# HV_DAC_8ch_FPGA_LVDS.net
KiCad netlist of a schematic drawn in Altium Designer
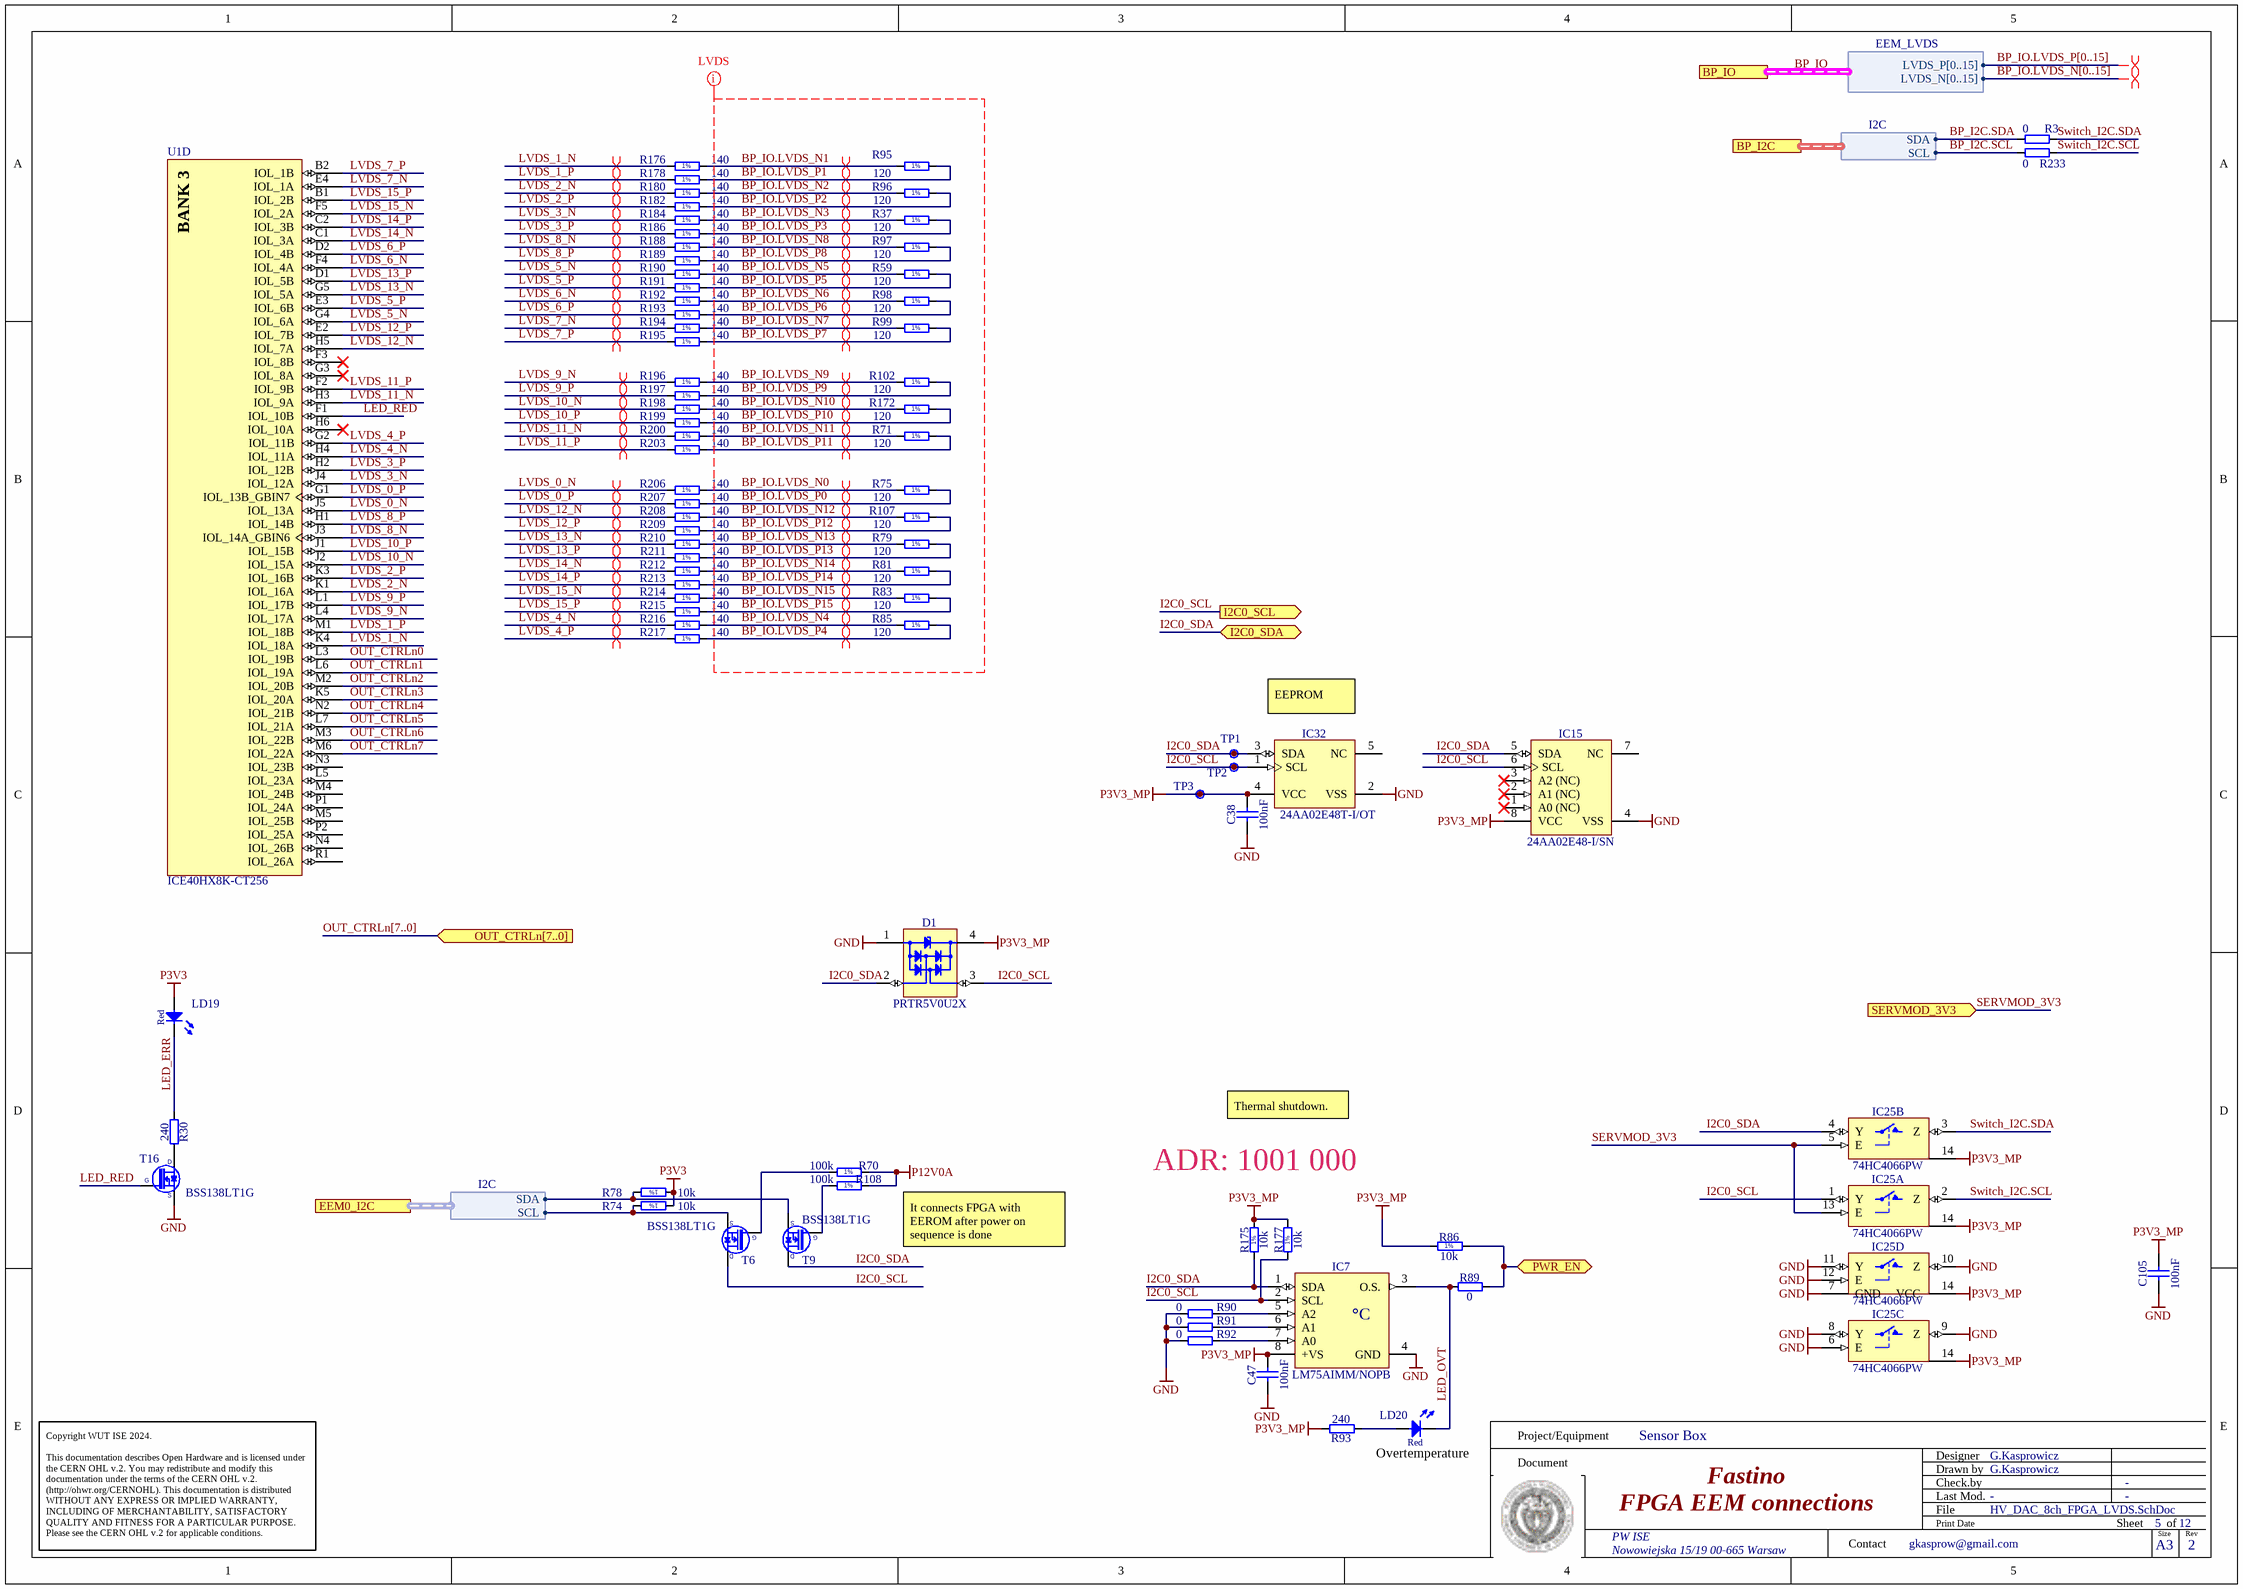
[diagram p0: HV_DAC_8ch_FPGA_LVDS.SchDoc]

(export (version "E")
  (design (tool "Eeschema 10.0.6"))
  (components
    (comp (ref "C38")
      (value "100nF")
      (footprint "CAPC1005X55N")
      (description "Non-polarised capacitor")
      (fields
        (field (name "PART NUMBER") "CC0402_100NF_16V_10%_X5R")
        (field (name "VOLTAGE") "16V")
        (field (name "AUTHOR") "CERN DEM JLC")
      )
      (libsource (lib "Capacitors") (part "Capacitor - non polarized"))
    )
    (comp (ref "C47")
      (value "100nF")
      (footprint "CAPC1005X55N")
      (description "Non-polarised capacitor")
      (fields
        (field (name "PART NUMBER") "CC0402_100NF_16V_10%_X5R")
        (field (name "VOLTAGE") "16V")
        (field (name "AUTHOR") "CERN DEM JLC")
      )
      (libsource (lib "Capacitors") (part "Capacitor - non polarized"))
    )
    (comp (ref "C105")
      (value "100nF")
      (footprint "CAPC1005X55N")
      (description "Non-polarised capacitor")
      (fields
        (field (name "PART NUMBER") "CC0402_100NF_16V_10%_X5R")
        (field (name "VOLTAGE") "16V")
        (field (name "AUTHOR") "CERN DEM JLC")
      )
      (libsource (lib "Capacitors") (part "Capacitor - non polarized"))
    )
    (comp (ref "D1")
      (value "PRTR5V0U2X")
      (footprint "SOT190P230X110-4N")
      (description "Ultra Low Capacitance Double Rail-to-Rail ESD Protection Diode")
      (fields
        (field (name "VOLTAGE") "5.5V")
        (field (name "MANUFACTURER") "NXP SEMICONDUCTORS")
        (field (name "AUTHOR") "CERN DEM JLC")
      )
      (libsource (lib "ICs And Semiconductors") (part "PRTR5V0U2X"))
    )
    (comp (ref "IC7")
      (value "LM75AIMM/NOPB")
      (footprint "SOP65P490X109-8N")
      (description "Digital Temperature Sensor and Thermal Watchdog with Two-Wire Interface")
      (fields (field (name "MANUFACTURER") "TEXAS INSTRUMENTS") (field (name "AUTHOR") "CERN DEM JLC"))
      (libsource (lib "ICs And Semiconductors") (part "LM75"))
    )
    (comp (ref "IC15")
      (value "24AA02E48-I/SN")
      (footprint "SOIC127P600X175-8N")
      (description "1.7V-5.5V, 2K I2C™ Serial EEPROMs with EUI-48™ Node Identity")
      (fields (field (name "MANUFACTURER") "MICROCHIP TECHNOLOGY") (field (name "AUTHOR") "CERN DEM MR"))
      (libsource (lib "ICS-logic") (part "MEM_24AA02E48-I/SN"))
    )
    (comp (ref "IC25")
      (value "74HC4066PW")
      (footprint "SOP65P640X110-14N")
      (fields (field (name "MANUFACTURER") "NXP SEMICONDUCTORS") (field (name "AUTHOR") "CERN DEM JLC"))
      (libsource (lib "ICs And Semiconductors") (part "4066"))
    )
    (comp (ref "IC32")
      (value "24AA02E48T-I/OT")
      (footprint "SOT95P280X145-5N")
      (description "1.7V-5.5V, 2K I2C Serial EEPROM With EUI-48 Node Identity")
      (fields (field (name "MANUFACTURER") "MICROCHIP TECHNOLOGY") (field (name "AUTHOR") "CERN DEM MR"))
      (libsource (lib "ICs And Semiconductors") (part "24AA02E48T-I/OT"))
    )
    (comp (ref "LD19")
      (value "Red")
      (footprint "LED_AVAGO_HSMC-C120")
      (description "LED Red 1C 2A")
      (fields
        (field (name "PART NUMBER") "LED_AVAGO_HSMC-C120")
        (field (name "MANUFACTURER") "AVAGO TECHNOLOGIES")
        (field (name "AUTHOR") "CERN DEM JMW")
      )
      (libsource (lib "ICs And Semiconductors") (part "LED Red 1C 2A"))
    )
    (comp (ref "LD20")
      (value "Red")
      (footprint "LED_AVAGO_HSMC-C120")
      (description "LED Red 1C 2A")
      (fields
        (field (name "PART NUMBER") "LED_AVAGO_HSMC-C120")
        (field (name "MANUFACTURER") "AVAGO TECHNOLOGIES")
        (field (name "AUTHOR") "CERN DEM JMW")
      )
      (libsource (lib "ICs And Semiconductors") (part "LED Red 1C 2A"))
    )
    (comp (ref "R3")
      (value "0")
      (footprint "RESC1005X40N")
      (description "Resistor")
      (fields
        (field (name "PART NUMBER") "R0402_0R_JUMPER")
        (field (name "MANUFACTURER") "GENERIC")
        (field (name "AUTHOR") "CERN DEM JLC")
      )
      (libsource (lib "Resistors") (part "Resistor"))
    )
    (comp (ref "R30")
      (value "240")
      (footprint "RESC1005X40N")
      (description "Resistor - 1%")
      (fields
        (field (name "PART NUMBER") "R0402_240R_1%_0.0625W_100PPM")
        (field (name "POWER") "0.0625W")
        (field (name "AUTHOR") "CERN DEM JLC")
      )
      (libsource (lib "Resistors") (part "Resistor - 1%"))
    )
    (comp (ref "R37")
      (value "120")
      (footprint "RESC1005X40N")
      (description "Resistor - 1%")
      (fields
        (field (name "PART NUMBER") "R0402_120R_1%_0.0625W_100PPM")
        (field (name "POWER") "0.0625W")
        (field (name "AUTHOR") "CERN DEM JLC")
      )
      (libsource (lib "Resistors") (part "Resistor - 1%"))
    )
    (comp (ref "R59")
      (value "120")
      (footprint "RESC1005X40N")
      (description "Resistor - 1%")
      (fields
        (field (name "PART NUMBER") "R0402_120R_1%_0.0625W_100PPM")
        (field (name "POWER") "0.0625W")
        (field (name "AUTHOR") "CERN DEM JLC")
      )
      (libsource (lib "Resistors") (part "Resistor - 1%"))
    )
    (comp (ref "R70")
      (value "100k")
      (footprint "RESC1005X40N")
      (description "Resistor - 1%")
      (fields
        (field (name "PART NUMBER") "R0402_100K_1%_0.0625W_100PPM")
        (field (name "POWER") "0.0625W")
        (field (name "AUTHOR") "CERN DEM JLC")
      )
      (libsource (lib "Resistors") (part "Resistor - 1%"))
    )
    (comp (ref "R71")
      (value "120")
      (footprint "RESC1005X40N")
      (description "Resistor - 1%")
      (fields
        (field (name "PART NUMBER") "R0402_120R_1%_0.0625W_100PPM")
        (field (name "POWER") "0.0625W")
        (field (name "AUTHOR") "CERN DEM JLC")
      )
      (libsource (lib "Resistors") (part "Resistor - 1%"))
    )
    (comp (ref "R74")
      (value "10k")
      (footprint "RESC1005X40N")
      (description "Resistor - 1%")
      (fields
        (field (name "PART NUMBER") "R0402_10K_1%_0.0625W_100PPM")
        (field (name "POWER") "0.0625W")
        (field (name "AUTHOR") "CERN DEM JLC")
      )
      (libsource (lib "Resistors") (part "Resistor - 1%"))
    )
    (comp (ref "R75")
      (value "120")
      (footprint "RESC1005X40N")
      (description "Resistor - 1%")
      (fields
        (field (name "PART NUMBER") "R0402_120R_1%_0.0625W_100PPM")
        (field (name "POWER") "0.0625W")
        (field (name "AUTHOR") "CERN DEM JLC")
      )
      (libsource (lib "Resistors") (part "Resistor - 1%"))
    )
    (comp (ref "R78")
      (value "10k")
      (footprint "RESC1005X40N")
      (description "Resistor - 1%")
      (fields
        (field (name "PART NUMBER") "R0402_10K_1%_0.0625W_100PPM")
        (field (name "POWER") "0.0625W")
        (field (name "AUTHOR") "CERN DEM JLC")
      )
      (libsource (lib "Resistors") (part "Resistor - 1%"))
    )
    (comp (ref "R79")
      (value "120")
      (footprint "RESC1005X40N")
      (description "Resistor - 1%")
      (fields
        (field (name "PART NUMBER") "R0402_120R_1%_0.0625W_100PPM")
        (field (name "POWER") "0.0625W")
        (field (name "AUTHOR") "CERN DEM JLC")
      )
      (libsource (lib "Resistors") (part "Resistor - 1%"))
    )
    (comp (ref "R81")
      (value "120")
      (footprint "RESC1005X40N")
      (description "Resistor - 1%")
      (fields
        (field (name "PART NUMBER") "R0402_120R_1%_0.0625W_100PPM")
        (field (name "POWER") "0.0625W")
        (field (name "AUTHOR") "CERN DEM JLC")
      )
      (libsource (lib "Resistors") (part "Resistor - 1%"))
    )
    (comp (ref "R83")
      (value "120")
      (footprint "RESC1005X40N")
      (description "Resistor - 1%")
      (fields
        (field (name "PART NUMBER") "R0402_120R_1%_0.0625W_100PPM")
        (field (name "POWER") "0.0625W")
        (field (name "AUTHOR") "CERN DEM JLC")
      )
      (libsource (lib "Resistors") (part "Resistor - 1%"))
    )
    (comp (ref "R85")
      (value "120")
      (footprint "RESC1005X40N")
      (description "Resistor - 1%")
      (fields
        (field (name "PART NUMBER") "R0402_120R_1%_0.0625W_100PPM")
        (field (name "POWER") "0.0625W")
        (field (name "AUTHOR") "CERN DEM JLC")
      )
      (libsource (lib "Resistors") (part "Resistor - 1%"))
    )
    (comp (ref "R86")
      (value "10k")
      (footprint "RESC1005X40N")
      (description "Resistor - 1%")
      (fields
        (field (name "PART NUMBER") "R0402_10K_1%_0.0625W_100PPM")
        (field (name "POWER") "0.0625W")
        (field (name "AUTHOR") "CERN DEM JLC")
      )
      (libsource (lib "Resistors") (part "Resistor - 1%"))
    )
    (comp (ref "R89")
      (value "0")
      (footprint "RESC1005X40N")
      (description "Resistor")
      (fields
        (field (name "PART NUMBER") "R0402_0R_JUMPER")
        (field (name "MANUFACTURER") "GENERIC")
        (field (name "AUTHOR") "CERN DEM JLC")
      )
      (libsource (lib "Resistors") (part "Resistor"))
    )
    (comp (ref "R90")
      (value "0")
      (footprint "RESC1005X40N")
      (description "Resistor")
      (fields
        (field (name "PART NUMBER") "R0402_0R_JUMPER")
        (field (name "MANUFACTURER") "GENERIC")
        (field (name "AUTHOR") "CERN DEM JLC")
      )
      (libsource (lib "Resistors") (part "Resistor"))
    )
    (comp (ref "R91")
      (value "0")
      (footprint "RESC1005X40N")
      (description "Resistor")
      (fields
        (field (name "PART NUMBER") "R0402_0R_JUMPER")
        (field (name "MANUFACTURER") "GENERIC")
        (field (name "AUTHOR") "CERN DEM JLC")
      )
      (libsource (lib "Resistors") (part "Resistor"))
    )
    (comp (ref "R92")
      (value "0")
      (footprint "RESC1005X40N")
      (description "Resistor")
      (fields
        (field (name "PART NUMBER") "R0402_0R_JUMPER")
        (field (name "MANUFACTURER") "GENERIC")
        (field (name "AUTHOR") "CERN DEM JLC")
      )
      (libsource (lib "Resistors") (part "Resistor"))
    )
    (comp (ref "R93")
      (value "240")
      (footprint "RESC1005X40N")
      (description "Resistor - 1%")
      (fields
        (field (name "PART NUMBER") "R0402_240R_1%_0.0625W_100PPM")
        (field (name "POWER") "0.0625W")
        (field (name "AUTHOR") "CERN DEM JLC")
      )
      (libsource (lib "Resistors") (part "Resistor - 1%"))
    )
    (comp (ref "R95")
      (value "120")
      (footprint "RESC1005X40N")
      (description "Resistor - 1%")
      (fields
        (field (name "PART NUMBER") "R0402_120R_1%_0.0625W_100PPM")
        (field (name "POWER") "0.0625W")
        (field (name "AUTHOR") "CERN DEM JLC")
      )
      (libsource (lib "Resistors") (part "Resistor - 1%"))
    )
    (comp (ref "R96")
      (value "120")
      (footprint "RESC1005X40N")
      (description "Resistor - 1%")
      (fields
        (field (name "PART NUMBER") "R0402_120R_1%_0.0625W_100PPM")
        (field (name "POWER") "0.0625W")
        (field (name "AUTHOR") "CERN DEM JLC")
      )
      (libsource (lib "Resistors") (part "Resistor - 1%"))
    )
    (comp (ref "R97")
      (value "120")
      (footprint "RESC1005X40N")
      (description "Resistor - 1%")
      (fields
        (field (name "PART NUMBER") "R0402_120R_1%_0.0625W_100PPM")
        (field (name "POWER") "0.0625W")
        (field (name "AUTHOR") "CERN DEM JLC")
      )
      (libsource (lib "Resistors") (part "Resistor - 1%"))
    )
    (comp (ref "R98")
      (value "120")
      (footprint "RESC1005X40N")
      (description "Resistor - 1%")
      (fields
        (field (name "PART NUMBER") "R0402_120R_1%_0.0625W_100PPM")
        (field (name "POWER") "0.0625W")
        (field (name "AUTHOR") "CERN DEM JLC")
      )
      (libsource (lib "Resistors") (part "Resistor - 1%"))
    )
    (comp (ref "R99")
      (value "120")
      (footprint "RESC1005X40N")
      (description "Resistor - 1%")
      (fields
        (field (name "PART NUMBER") "R0402_120R_1%_0.0625W_100PPM")
        (field (name "POWER") "0.0625W")
        (field (name "AUTHOR") "CERN DEM JLC")
      )
      (libsource (lib "Resistors") (part "Resistor - 1%"))
    )
    (comp (ref "R102")
      (value "120")
      (footprint "RESC1005X40N")
      (description "Resistor - 1%")
      (fields
        (field (name "PART NUMBER") "R0402_120R_1%_0.0625W_100PPM")
        (field (name "POWER") "0.0625W")
        (field (name "AUTHOR") "CERN DEM JLC")
      )
      (libsource (lib "Resistors") (part "Resistor - 1%"))
    )
    (comp (ref "R107")
      (value "120")
      (footprint "RESC1005X40N")
      (description "Resistor - 1%")
      (fields
        (field (name "PART NUMBER") "R0402_120R_1%_0.0625W_100PPM")
        (field (name "POWER") "0.0625W")
        (field (name "AUTHOR") "CERN DEM JLC")
      )
      (libsource (lib "Resistors") (part "Resistor - 1%"))
    )
    (comp (ref "R108")
      (value "100k")
      (footprint "RESC1005X40N")
      (description "Resistor - 1%")
      (fields
        (field (name "PART NUMBER") "R0402_100K_1%_0.0625W_100PPM")
        (field (name "POWER") "0.0625W")
        (field (name "AUTHOR") "CERN DEM JLC")
      )
      (libsource (lib "Resistors") (part "Resistor - 1%"))
    )
    (comp (ref "R172")
      (value "120")
      (footprint "RESC1005X40N")
      (description "Resistor - 1%")
      (fields
        (field (name "PART NUMBER") "R0402_120R_1%_0.0625W_100PPM")
        (field (name "POWER") "0.0625W")
        (field (name "AUTHOR") "CERN DEM JLC")
      )
      (libsource (lib "Resistors") (part "Resistor - 1%"))
    )
    (comp (ref "R175")
      (value "10k")
      (footprint "RESC1005X40N")
      (description "Resistor - 1%")
      (fields
        (field (name "PART NUMBER") "R0402_10K_1%_0.0625W_100PPM")
        (field (name "POWER") "0.0625W")
        (field (name "AUTHOR") "CERN DEM JLC")
      )
      (libsource (lib "Resistors") (part "Resistor - 1%"))
    )
    (comp (ref "R176")
      (value "140")
      (footprint "RESC0603X28N")
      (description "Resistor - 1%")
      (fields
        (field (name "PART NUMBER") "R0201_140R_1%_0.05W_200PPM")
        (field (name "POWER") "0.05W")
        (field (name "AUTHOR") "CERN DEM MR")
      )
      (libsource (lib "Resistors") (part "Resistor - 1%"))
    )
    (comp (ref "R177")
      (value "10k")
      (footprint "RESC1005X40N")
      (description "Resistor - 1%")
      (fields
        (field (name "PART NUMBER") "R0402_10K_1%_0.0625W_100PPM")
        (field (name "POWER") "0.0625W")
        (field (name "AUTHOR") "CERN DEM JLC")
      )
      (libsource (lib "Resistors") (part "Resistor - 1%"))
    )
    (comp (ref "R178")
      (value "140")
      (footprint "RESC0603X28N")
      (description "Resistor - 1%")
      (fields
        (field (name "PART NUMBER") "R0201_140R_1%_0.05W_200PPM")
        (field (name "POWER") "0.05W")
        (field (name "AUTHOR") "CERN DEM MR")
      )
      (libsource (lib "Resistors") (part "Resistor - 1%"))
    )
    (comp (ref "R180")
      (value "140")
      (footprint "RESC0603X28N")
      (description "Resistor - 1%")
      (fields
        (field (name "PART NUMBER") "R0201_140R_1%_0.05W_200PPM")
        (field (name "POWER") "0.05W")
        (field (name "AUTHOR") "CERN DEM MR")
      )
      (libsource (lib "Resistors") (part "Resistor - 1%"))
    )
    (comp (ref "R182")
      (value "140")
      (footprint "RESC0603X28N")
      (description "Resistor - 1%")
      (fields
        (field (name "PART NUMBER") "R0201_140R_1%_0.05W_200PPM")
        (field (name "POWER") "0.05W")
        (field (name "AUTHOR") "CERN DEM MR")
      )
      (libsource (lib "Resistors") (part "Resistor - 1%"))
    )
    (comp (ref "R184")
      (value "140")
      (footprint "RESC0603X28N")
      (description "Resistor - 1%")
      (fields
        (field (name "PART NUMBER") "R0201_140R_1%_0.05W_200PPM")
        (field (name "POWER") "0.05W")
        (field (name "AUTHOR") "CERN DEM MR")
      )
      (libsource (lib "Resistors") (part "Resistor - 1%"))
    )
    (comp (ref "R186")
      (value "140")
      (footprint "RESC0603X28N")
      (description "Resistor - 1%")
      (fields
        (field (name "PART NUMBER") "R0201_140R_1%_0.05W_200PPM")
        (field (name "POWER") "0.05W")
        (field (name "AUTHOR") "CERN DEM MR")
      )
      (libsource (lib "Resistors") (part "Resistor - 1%"))
    )
    (comp (ref "R188")
      (value "140")
      (footprint "RESC0603X28N")
      (description "Resistor - 1%")
      (fields
        (field (name "PART NUMBER") "R0201_140R_1%_0.05W_200PPM")
        (field (name "POWER") "0.05W")
        (field (name "AUTHOR") "CERN DEM MR")
      )
      (libsource (lib "Resistors") (part "Resistor - 1%"))
    )
    (comp (ref "R189")
      (value "140")
      (footprint "RESC0603X28N")
      (description "Resistor - 1%")
      (fields
        (field (name "PART NUMBER") "R0201_140R_1%_0.05W_200PPM")
        (field (name "POWER") "0.05W")
        (field (name "AUTHOR") "CERN DEM MR")
      )
      (libsource (lib "Resistors") (part "Resistor - 1%"))
    )
    (comp (ref "R190")
      (value "140")
      (footprint "RESC0603X28N")
      (description "Resistor - 1%")
      (fields
        (field (name "PART NUMBER") "R0201_140R_1%_0.05W_200PPM")
        (field (name "POWER") "0.05W")
        (field (name "AUTHOR") "CERN DEM MR")
      )
      (libsource (lib "Resistors") (part "Resistor - 1%"))
    )
    (comp (ref "R191")
      (value "140")
      (footprint "RESC0603X28N")
      (description "Resistor - 1%")
      (fields
        (field (name "PART NUMBER") "R0201_140R_1%_0.05W_200PPM")
        (field (name "POWER") "0.05W")
        (field (name "AUTHOR") "CERN DEM MR")
      )
      (libsource (lib "Resistors") (part "Resistor - 1%"))
    )
    (comp (ref "R192")
      (value "140")
      (footprint "RESC0603X28N")
      (description "Resistor - 1%")
      (fields
        (field (name "PART NUMBER") "R0201_140R_1%_0.05W_200PPM")
        (field (name "POWER") "0.05W")
        (field (name "AUTHOR") "CERN DEM MR")
      )
      (libsource (lib "Resistors") (part "Resistor - 1%"))
    )
    (comp (ref "R193")
      (value "140")
      (footprint "RESC0603X28N")
      (description "Resistor - 1%")
      (fields
        (field (name "PART NUMBER") "R0201_140R_1%_0.05W_200PPM")
        (field (name "POWER") "0.05W")
        (field (name "AUTHOR") "CERN DEM MR")
      )
      (libsource (lib "Resistors") (part "Resistor - 1%"))
    )
    (comp (ref "R194")
      (value "140")
      (footprint "RESC0603X28N")
      (description "Resistor - 1%")
      (fields
        (field (name "PART NUMBER") "R0201_140R_1%_0.05W_200PPM")
        (field (name "POWER") "0.05W")
        (field (name "AUTHOR") "CERN DEM MR")
      )
      (libsource (lib "Resistors") (part "Resistor - 1%"))
    )
    (comp (ref "R195")
      (value "140")
      (footprint "RESC0603X28N")
      (description "Resistor - 1%")
      (fields
        (field (name "PART NUMBER") "R0201_140R_1%_0.05W_200PPM")
        (field (name "POWER") "0.05W")
        (field (name "AUTHOR") "CERN DEM MR")
      )
      (libsource (lib "Resistors") (part "Resistor - 1%"))
    )
    (comp (ref "R196")
      (value "140")
      (footprint "RESC0603X28N")
      (description "Resistor - 1%")
      (fields
        (field (name "PART NUMBER") "R0201_140R_1%_0.05W_200PPM")
        (field (name "POWER") "0.05W")
        (field (name "AUTHOR") "CERN DEM MR")
      )
      (libsource (lib "Resistors") (part "Resistor - 1%"))
    )
    (comp (ref "R197")
      (value "140")
      (footprint "RESC0603X28N")
      (description "Resistor - 1%")
      (fields
        (field (name "PART NUMBER") "R0201_140R_1%_0.05W_200PPM")
        (field (name "POWER") "0.05W")
        (field (name "AUTHOR") "CERN DEM MR")
      )
      (libsource (lib "Resistors") (part "Resistor - 1%"))
    )
    (comp (ref "R198")
      (value "140")
      (footprint "RESC0603X28N")
      (description "Resistor - 1%")
      (fields
        (field (name "PART NUMBER") "R0201_140R_1%_0.05W_200PPM")
        (field (name "POWER") "0.05W")
        (field (name "AUTHOR") "CERN DEM MR")
      )
      (libsource (lib "Resistors") (part "Resistor - 1%"))
    )
    (comp (ref "R199")
      (value "140")
      (footprint "RESC0603X28N")
      (description "Resistor - 1%")
      (fields
        (field (name "PART NUMBER") "R0201_140R_1%_0.05W_200PPM")
        (field (name "POWER") "0.05W")
        (field (name "AUTHOR") "CERN DEM MR")
      )
      (libsource (lib "Resistors") (part "Resistor - 1%"))
    )
    (comp (ref "R200")
      (value "140")
      (footprint "RESC0603X28N")
      (description "Resistor - 1%")
      (fields
        (field (name "PART NUMBER") "R0201_140R_1%_0.05W_200PPM")
        (field (name "POWER") "0.05W")
        (field (name "AUTHOR") "CERN DEM MR")
      )
      (libsource (lib "Resistors") (part "Resistor - 1%"))
    )
    (comp (ref "R203")
      (value "140")
      (footprint "RESC0603X28N")
      (description "Resistor - 1%")
      (fields
        (field (name "PART NUMBER") "R0201_140R_1%_0.05W_200PPM")
        (field (name "POWER") "0.05W")
        (field (name "AUTHOR") "CERN DEM MR")
      )
      (libsource (lib "Resistors") (part "Resistor - 1%"))
    )
    (comp (ref "R206")
      (value "140")
      (footprint "RESC0603X28N")
      (description "Resistor - 1%")
      (fields
        (field (name "PART NUMBER") "R0201_140R_1%_0.05W_200PPM")
        (field (name "POWER") "0.05W")
        (field (name "AUTHOR") "CERN DEM MR")
      )
      (libsource (lib "Resistors") (part "Resistor - 1%"))
    )
    (comp (ref "R207")
      (value "140")
      (footprint "RESC0603X28N")
      (description "Resistor - 1%")
      (fields
        (field (name "PART NUMBER") "R0201_140R_1%_0.05W_200PPM")
        (field (name "POWER") "0.05W")
        (field (name "AUTHOR") "CERN DEM MR")
      )
      (libsource (lib "Resistors") (part "Resistor - 1%"))
    )
    (comp (ref "R208")
      (value "140")
      (footprint "RESC0603X28N")
      (description "Resistor - 1%")
      (fields
        (field (name "PART NUMBER") "R0201_140R_1%_0.05W_200PPM")
        (field (name "POWER") "0.05W")
        (field (name "AUTHOR") "CERN DEM MR")
      )
      (libsource (lib "Resistors") (part "Resistor - 1%"))
    )
    (comp (ref "R209")
      (value "140")
      (footprint "RESC0603X28N")
      (description "Resistor - 1%")
      (fields
        (field (name "PART NUMBER") "R0201_140R_1%_0.05W_200PPM")
        (field (name "POWER") "0.05W")
        (field (name "AUTHOR") "CERN DEM MR")
      )
      (libsource (lib "Resistors") (part "Resistor - 1%"))
    )
    (comp (ref "R210")
      (value "140")
      (footprint "RESC0603X28N")
      (description "Resistor - 1%")
      (fields
        (field (name "PART NUMBER") "R0201_140R_1%_0.05W_200PPM")
        (field (name "POWER") "0.05W")
        (field (name "AUTHOR") "CERN DEM MR")
      )
      (libsource (lib "Resistors") (part "Resistor - 1%"))
    )
    (comp (ref "R211")
      (value "140")
      (footprint "RESC0603X28N")
      (description "Resistor - 1%")
      (fields
        (field (name "PART NUMBER") "R0201_140R_1%_0.05W_200PPM")
        (field (name "POWER") "0.05W")
        (field (name "AUTHOR") "CERN DEM MR")
      )
      (libsource (lib "Resistors") (part "Resistor - 1%"))
    )
    (comp (ref "R212")
      (value "140")
      (footprint "RESC0603X28N")
      (description "Resistor - 1%")
      (fields
        (field (name "PART NUMBER") "R0201_140R_1%_0.05W_200PPM")
        (field (name "POWER") "0.05W")
        (field (name "AUTHOR") "CERN DEM MR")
      )
      (libsource (lib "Resistors") (part "Resistor - 1%"))
    )
    (comp (ref "R213")
      (value "140")
      (footprint "RESC0603X28N")
      (description "Resistor - 1%")
      (fields
        (field (name "PART NUMBER") "R0201_140R_1%_0.05W_200PPM")
        (field (name "POWER") "0.05W")
        (field (name "AUTHOR") "CERN DEM MR")
      )
      (libsource (lib "Resistors") (part "Resistor - 1%"))
    )
    (comp (ref "R214")
      (value "140")
      (footprint "RESC0603X28N")
      (description "Resistor - 1%")
      (fields
        (field (name "PART NUMBER") "R0201_140R_1%_0.05W_200PPM")
        (field (name "POWER") "0.05W")
        (field (name "AUTHOR") "CERN DEM MR")
      )
      (libsource (lib "Resistors") (part "Resistor - 1%"))
    )
    (comp (ref "R215")
      (value "140")
      (footprint "RESC0603X28N")
      (description "Resistor - 1%")
      (fields
        (field (name "PART NUMBER") "R0201_140R_1%_0.05W_200PPM")
        (field (name "POWER") "0.05W")
        (field (name "AUTHOR") "CERN DEM MR")
      )
      (libsource (lib "Resistors") (part "Resistor - 1%"))
    )
    (comp (ref "R216")
      (value "140")
      (footprint "RESC0603X28N")
      (description "Resistor - 1%")
      (fields
        (field (name "PART NUMBER") "R0201_140R_1%_0.05W_200PPM")
        (field (name "POWER") "0.05W")
        (field (name "AUTHOR") "CERN DEM MR")
      )
      (libsource (lib "Resistors") (part "Resistor - 1%"))
    )
    (comp (ref "R217")
      (value "140")
      (footprint "RESC0603X28N")
      (description "Resistor - 1%")
      (fields
        (field (name "PART NUMBER") "R0201_140R_1%_0.05W_200PPM")
        (field (name "POWER") "0.05W")
        (field (name "AUTHOR") "CERN DEM MR")
      )
      (libsource (lib "Resistors") (part "Resistor - 1%"))
    )
    (comp (ref "R233")
      (value "0")
      (footprint "RESC1005X40N")
      (description "Resistor")
      (fields
        (field (name "PART NUMBER") "R0402_0R_JUMPER")
        (field (name "MANUFACTURER") "GENERIC")
        (field (name "AUTHOR") "CERN DEM JLC")
      )
      (libsource (lib "Resistors") (part "Resistor"))
    )
    (comp (ref "T6")
      (value "BSS138LT1G")
      (footprint "SOT95P240X110-3N")
      (description "N-CHANNEL MOSFET WITH DIODE")
      (fields (field (name "MANUFACTURER") "ON SEMICONDUCTOR") (field (name "AUTHOR") "CERN DEM JLC"))
      (libsource (lib "ICs And Semiconductors") (part "N-MOSFET-D 1G 2S 3D"))
    )
    (comp (ref "T9")
      (value "BSS138LT1G")
      (footprint "SOT95P240X110-3N")
      (description "N-CHANNEL MOSFET WITH DIODE")
      (fields (field (name "MANUFACTURER") "ON SEMICONDUCTOR") (field (name "AUTHOR") "CERN DEM JLC"))
      (libsource (lib "ICs And Semiconductors") (part "N-MOSFET-D 1G 2S 3D"))
    )
    (comp (ref "T16")
      (value "BSS138LT1G")
      (footprint "SOT95P240X110-3N")
      (description "N-CHANNEL MOSFET WITH DIODE")
      (fields (field (name "MANUFACTURER") "ON SEMICONDUCTOR") (field (name "AUTHOR") "CERN DEM JLC"))
      (libsource (lib "") (part "N-MOSFET-D 1G 2S 3D_1"))
    )
    (comp (ref "TP1")
      (value "Test Point")
      (footprint "TPS127")
      (fields (field (name "PART NUMBER") "SMD_PAD_1.27X1.27MM") (field (name "AUTHOR") "CERN DEM JLC"))
      (libsource (lib "Eletro-mechanical") (part "Test Point"))
    )
    (comp (ref "TP2")
      (value "Test Point")
      (footprint "TPS127")
      (fields (field (name "PART NUMBER") "SMD_PAD_1.27X1.27MM") (field (name "AUTHOR") "CERN DEM JLC"))
      (libsource (lib "Eletro-mechanical") (part "Test Point"))
    )
    (comp (ref "TP3")
      (value "Test Point")
      (footprint "TPS127")
      (fields (field (name "PART NUMBER") "SMD_PAD_1.27X1.27MM") (field (name "AUTHOR") "CERN DEM JLC"))
      (libsource (lib "Eletro-mechanical") (part "Test Point"))
    )
    (comp (ref "U1")
      (value "ICE40HX8K-CT256")
      (footprint "LATC-caBGA-256")
      (fields (field (name "MANUFACTURER") "Lattice Semiconductor"))
      (libsource (lib "Altium Content Vault") (part "LATC-HX8K-caBGA-256"))
    )
  )
  (nets
    (net (code "3") (name "/BP_I2C.SCL") (class "Default")
      (node (ref "R233") (pin "1") (pinfunction "1_1") (pintype "passive"))
    )
    (net (code "4") (name "/BP_I2C.SDA") (class "Default")
      (node (ref "R3") (pin "1") (pinfunction "1_1") (pintype "passive"))
    )
    (net (code "5") (name "/BP_IO.LVDS_N0") (class "Default")
      (node (ref "R206") (pin "2") (pinfunction "2_2") (pintype "passive"))
      (node (ref "R75") (pin "1") (pinfunction "1_1") (pintype "passive"))
    )
    (net (code "6") (name "/BP_IO.LVDS_N1") (class "Default")
      (node (ref "R176") (pin "2") (pinfunction "2_2") (pintype "passive"))
      (node (ref "R95") (pin "1") (pinfunction "1_1") (pintype "passive"))
    )
    (net (code "7") (name "/BP_IO.LVDS_N2") (class "Default")
      (node (ref "R180") (pin "2") (pinfunction "2_2") (pintype "passive"))
      (node (ref "R96") (pin "1") (pinfunction "1_1") (pintype "passive"))
    )
    (net (code "8") (name "/BP_IO.LVDS_N3") (class "Default")
      (node (ref "R184") (pin "2") (pinfunction "2_2") (pintype "passive"))
      (node (ref "R37") (pin "1") (pinfunction "1_1") (pintype "passive"))
    )
    (net (code "9") (name "/BP_IO.LVDS_N4") (class "Default")
      (node (ref "R216") (pin "2") (pinfunction "2_2") (pintype "passive"))
      (node (ref "R85") (pin "1") (pinfunction "1_1") (pintype "passive"))
    )
    (net (code "10") (name "/BP_IO.LVDS_N5") (class "Default")
      (node (ref "R190") (pin "2") (pinfunction "2_2") (pintype "passive"))
      (node (ref "R59") (pin "1") (pinfunction "1_1") (pintype "passive"))
    )
    (net (code "11") (name "/BP_IO.LVDS_N6") (class "Default")
      (node (ref "R192") (pin "2") (pinfunction "2_2") (pintype "passive"))
      (node (ref "R98") (pin "1") (pinfunction "1_1") (pintype "passive"))
    )
    (net (code "12") (name "/BP_IO.LVDS_N7") (class "Default")
      (node (ref "R194") (pin "2") (pinfunction "2_2") (pintype "passive"))
      (node (ref "R99") (pin "1") (pinfunction "1_1") (pintype "passive"))
    )
    (net (code "13") (name "/BP_IO.LVDS_N8") (class "Default")
      (node (ref "R188") (pin "2") (pinfunction "2_2") (pintype "passive"))
      (node (ref "R97") (pin "1") (pinfunction "1_1") (pintype "passive"))
    )
    (net (code "14") (name "/BP_IO.LVDS_N9") (class "Default")
      (node (ref "R102") (pin "1") (pinfunction "1_1") (pintype "passive"))
      (node (ref "R196") (pin "2") (pinfunction "2_2") (pintype "passive"))
    )
    (net (code "15") (name "/BP_IO.LVDS_N10") (class "Default")
      (node (ref "R172") (pin "1") (pinfunction "1_1") (pintype "passive"))
      (node (ref "R198") (pin "2") (pinfunction "2_2") (pintype "passive"))
    )
    (net (code "16") (name "/BP_IO.LVDS_N11") (class "Default")
      (node (ref "R200") (pin "2") (pinfunction "2_2") (pintype "passive"))
      (node (ref "R71") (pin "1") (pinfunction "1_1") (pintype "passive"))
    )
    (net (code "17") (name "/BP_IO.LVDS_N12") (class "Default")
      (node (ref "R107") (pin "1") (pinfunction "1_1") (pintype "passive"))
      (node (ref "R208") (pin "2") (pinfunction "2_2") (pintype "passive"))
    )
    (net (code "18") (name "/BP_IO.LVDS_N13") (class "Default")
      (node (ref "R210") (pin "2") (pinfunction "2_2") (pintype "passive"))
      (node (ref "R79") (pin "1") (pinfunction "1_1") (pintype "passive"))
    )
    (net (code "19") (name "/BP_IO.LVDS_N14") (class "Default")
      (node (ref "R212") (pin "2") (pinfunction "2_2") (pintype "passive"))
      (node (ref "R81") (pin "1") (pinfunction "1_1") (pintype "passive"))
    )
    (net (code "20") (name "/BP_IO.LVDS_N15") (class "Default")
      (node (ref "R214") (pin "2") (pinfunction "2_2") (pintype "passive"))
      (node (ref "R83") (pin "1") (pinfunction "1_1") (pintype "passive"))
    )
    (net (code "22") (name "/BP_IO.LVDS_P0") (class "Default")
      (node (ref "R207") (pin "2") (pinfunction "2_2") (pintype "passive"))
      (node (ref "R75") (pin "2") (pinfunction "2_2") (pintype "passive"))
    )
    (net (code "23") (name "/BP_IO.LVDS_P1") (class "Default")
      (node (ref "R178") (pin "2") (pinfunction "2_2") (pintype "passive"))
      (node (ref "R95") (pin "2") (pinfunction "2_2") (pintype "passive"))
    )
    (net (code "24") (name "/BP_IO.LVDS_P2") (class "Default")
      (node (ref "R182") (pin "2") (pinfunction "2_2") (pintype "passive"))
      (node (ref "R96") (pin "2") (pinfunction "2_2") (pintype "passive"))
    )
    (net (code "25") (name "/BP_IO.LVDS_P3") (class "Default")
      (node (ref "R186") (pin "2") (pinfunction "2_2") (pintype "passive"))
      (node (ref "R37") (pin "2") (pinfunction "2_2") (pintype "passive"))
    )
    (net (code "26") (name "/BP_IO.LVDS_P4") (class "Default")
      (node (ref "R217") (pin "2") (pinfunction "2_2") (pintype "passive"))
      (node (ref "R85") (pin "2") (pinfunction "2_2") (pintype "passive"))
    )
    (net (code "27") (name "/BP_IO.LVDS_P5") (class "Default")
      (node (ref "R191") (pin "2") (pinfunction "2_2") (pintype "passive"))
      (node (ref "R59") (pin "2") (pinfunction "2_2") (pintype "passive"))
    )
    (net (code "28") (name "/BP_IO.LVDS_P6") (class "Default")
      (node (ref "R193") (pin "2") (pinfunction "2_2") (pintype "passive"))
      (node (ref "R98") (pin "2") (pinfunction "2_2") (pintype "passive"))
    )
    (net (code "29") (name "/BP_IO.LVDS_P7") (class "Default")
      (node (ref "R195") (pin "2") (pinfunction "2_2") (pintype "passive"))
      (node (ref "R99") (pin "2") (pinfunction "2_2") (pintype "passive"))
    )
    (net (code "30") (name "/BP_IO.LVDS_P8") (class "Default")
      (node (ref "R189") (pin "2") (pinfunction "2_2") (pintype "passive"))
      (node (ref "R97") (pin "2") (pinfunction "2_2") (pintype "passive"))
    )
    (net (code "31") (name "/BP_IO.LVDS_P9") (class "Default")
      (node (ref "R102") (pin "2") (pinfunction "2_2") (pintype "passive"))
      (node (ref "R197") (pin "2") (pinfunction "2_2") (pintype "passive"))
    )
    (net (code "32") (name "/BP_IO.LVDS_P10") (class "Default")
      (node (ref "R172") (pin "2") (pinfunction "2_2") (pintype "passive"))
      (node (ref "R199") (pin "2") (pinfunction "2_2") (pintype "passive"))
    )
    (net (code "33") (name "/BP_IO.LVDS_P11") (class "Default")
      (node (ref "R203") (pin "2") (pinfunction "2_2") (pintype "passive"))
      (node (ref "R71") (pin "2") (pinfunction "2_2") (pintype "passive"))
    )
    (net (code "34") (name "/BP_IO.LVDS_P12") (class "Default")
      (node (ref "R107") (pin "2") (pinfunction "2_2") (pintype "passive"))
      (node (ref "R209") (pin "2") (pinfunction "2_2") (pintype "passive"))
    )
    (net (code "35") (name "/BP_IO.LVDS_P13") (class "Default")
      (node (ref "R211") (pin "2") (pinfunction "2_2") (pintype "passive"))
      (node (ref "R79") (pin "2") (pinfunction "2_2") (pintype "passive"))
    )
    (net (code "36") (name "/BP_IO.LVDS_P14") (class "Default")
      (node (ref "R213") (pin "2") (pinfunction "2_2") (pintype "passive"))
      (node (ref "R81") (pin "2") (pinfunction "2_2") (pintype "passive"))
    )
    (net (code "37") (name "/BP_IO.LVDS_P15") (class "Default")
      (node (ref "R215") (pin "2") (pinfunction "2_2") (pintype "passive"))
      (node (ref "R83") (pin "2") (pinfunction "2_2") (pintype "passive"))
    )
    (net (code "40") (name "/I2C0_SCL") (class "Default")
      (node (ref "D1") (pin "3") (pinfunction "I/O2_3") (pintype "bidirectional"))
      (node (ref "IC15") (pin "6") (pinfunction "SCL_6") (pintype "input"))
      (node (ref "IC25") (pin "1") (pinfunction "Y_1") (pintype "bidirectional"))
      (node (ref "IC32") (pin "1") (pinfunction "SCL_1") (pintype "input"))
      (node (ref "IC7") (pin "2") (pinfunction "SCL_2") (pintype "input"))
      (node (ref "R177") (pin "1") (pinfunction "1_1") (pintype "passive"))
      (node (ref "T6") (pin "3") (pinfunction "D_3") (pintype "passive"))
      (node (ref "TP2") (pin "1") (pinfunction "1_1") (pintype "bidirectional"))
    )
    (net (code "41") (name "/I2C0_SDA") (class "Default")
      (node (ref "D1") (pin "2") (pinfunction "I/O1_2") (pintype "bidirectional"))
      (node (ref "IC15") (pin "5") (pinfunction "SDA_5") (pintype "bidirectional"))
      (node (ref "IC25") (pin "4") (pinfunction "Y_4") (pintype "bidirectional"))
      (node (ref "IC32") (pin "3") (pinfunction "SDA_3") (pintype "bidirectional"))
      (node (ref "IC7") (pin "1") (pinfunction "SDA_1") (pintype "bidirectional"))
      (node (ref "R175") (pin "1") (pinfunction "1_1") (pintype "passive"))
      (node (ref "T9") (pin "3") (pinfunction "D_3") (pintype "passive"))
      (node (ref "TP1") (pin "1") (pinfunction "1_1") (pintype "bidirectional"))
    )
    (net (code "42") (name "/LED_ERR") (class "Default")
      (node (ref "LD19") (pin "1") (pinfunction "C_1") (pintype "passive"))
      (node (ref "R30") (pin "1") (pinfunction "1_1") (pintype "passive"))
    )
    (net (code "43") (name "/LED_OVT") (class "Default")
      (node (ref "IC7") (pin "3") (pinfunction "O.S._3") (pintype "output"))
      (node (ref "LD20") (pin "1") (pinfunction "C_1") (pintype "passive"))
      (node (ref "R89") (pin "1") (pinfunction "1_1") (pintype "passive"))
    )
    (net (code "44") (name "/LED_RED") (class "Default")
      (node (ref "T16") (pin "1") (pinfunction "G_1") (pintype "passive"))
      (node (ref "U1") (pin "F1") (pinfunction "IOL_10B_F1") (pintype "bidirectional"))
    )
    (net (code "45") (name "/LVDS_0_N") (class "Default")
      (node (ref "R206") (pin "1") (pinfunction "1_1") (pintype "passive"))
      (node (ref "U1") (pin "J5") (pinfunction "IOL_13A_J5") (pintype "bidirectional"))
    )
    (net (code "46") (name "/LVDS_0_P") (class "Default")
      (node (ref "R207") (pin "1") (pinfunction "1_1") (pintype "passive"))
      (node (ref "U1") (pin "G1") (pinfunction "IOL_13B_GBIN7_G1") (pintype "bidirectional"))
    )
    (net (code "47") (name "/LVDS_1_N") (class "Default")
      (node (ref "R176") (pin "1") (pinfunction "1_1") (pintype "passive"))
      (node (ref "U1") (pin "K4") (pinfunction "IOL_18A_K4") (pintype "bidirectional"))
    )
    (net (code "48") (name "/LVDS_1_P") (class "Default")
      (node (ref "R178") (pin "1") (pinfunction "1_1") (pintype "passive"))
      (node (ref "U1") (pin "M1") (pinfunction "IOL_18B_M1") (pintype "bidirectional"))
    )
    (net (code "49") (name "/LVDS_2_N") (class "Default")
      (node (ref "R180") (pin "1") (pinfunction "1_1") (pintype "passive"))
      (node (ref "U1") (pin "K1") (pinfunction "IOL_16A_K1") (pintype "bidirectional"))
    )
    (net (code "50") (name "/LVDS_2_P") (class "Default")
      (node (ref "R182") (pin "1") (pinfunction "1_1") (pintype "passive"))
      (node (ref "U1") (pin "K3") (pinfunction "IOL_16B_K3") (pintype "bidirectional"))
    )
    (net (code "51") (name "/LVDS_3_N") (class "Default")
      (node (ref "R184") (pin "1") (pinfunction "1_1") (pintype "passive"))
      (node (ref "U1") (pin "J4") (pinfunction "IOL_12A_J4") (pintype "bidirectional"))
    )
    (net (code "52") (name "/LVDS_3_P") (class "Default")
      (node (ref "R186") (pin "1") (pinfunction "1_1") (pintype "passive"))
      (node (ref "U1") (pin "H2") (pinfunction "IOL_12B_H2") (pintype "bidirectional"))
    )
    (net (code "53") (name "/LVDS_4_N") (class "Default")
      (node (ref "R216") (pin "1") (pinfunction "1_1") (pintype "passive"))
      (node (ref "U1") (pin "H4") (pinfunction "IOL_11A_H4") (pintype "bidirectional"))
    )
    (net (code "54") (name "/LVDS_4_P") (class "Default")
      (node (ref "R217") (pin "1") (pinfunction "1_1") (pintype "passive"))
      (node (ref "U1") (pin "G2") (pinfunction "IOL_11B_G2") (pintype "bidirectional"))
    )
    (net (code "55") (name "/LVDS_5_N") (class "Default")
      (node (ref "R190") (pin "1") (pinfunction "1_1") (pintype "passive"))
      (node (ref "U1") (pin "G4") (pinfunction "IOL_6A_G4") (pintype "bidirectional"))
    )
    (net (code "56") (name "/LVDS_5_P") (class "Default")
      (node (ref "R191") (pin "1") (pinfunction "1_1") (pintype "passive"))
      (node (ref "U1") (pin "E3") (pinfunction "IOL_6B_E3") (pintype "bidirectional"))
    )
    (net (code "57") (name "/LVDS_6_N") (class "Default")
      (node (ref "R192") (pin "1") (pinfunction "1_1") (pintype "passive"))
      (node (ref "U1") (pin "F4") (pinfunction "IOL_4A_F4") (pintype "bidirectional"))
    )
    (net (code "58") (name "/LVDS_6_P") (class "Default")
      (node (ref "R193") (pin "1") (pinfunction "1_1") (pintype "passive"))
      (node (ref "U1") (pin "D2") (pinfunction "IOL_4B_D2") (pintype "bidirectional"))
    )
    (net (code "59") (name "/LVDS_7_N") (class "Default")
      (node (ref "R194") (pin "1") (pinfunction "1_1") (pintype "passive"))
      (node (ref "U1") (pin "E4") (pinfunction "IOL_1A_E4") (pintype "bidirectional"))
    )
    (net (code "60") (name "/LVDS_7_P") (class "Default")
      (node (ref "R195") (pin "1") (pinfunction "1_1") (pintype "passive"))
      (node (ref "U1") (pin "B2") (pinfunction "IOL_1B_B2") (pintype "bidirectional"))
    )
    (net (code "61") (name "/LVDS_8_N") (class "Default")
      (node (ref "R188") (pin "1") (pinfunction "1_1") (pintype "passive"))
      (node (ref "U1") (pin "J3") (pinfunction "IOL_14A_GBIN6_J3") (pintype "bidirectional"))
    )
    (net (code "62") (name "/LVDS_8_P") (class "Default")
      (node (ref "R189") (pin "1") (pinfunction "1_1") (pintype "passive"))
      (node (ref "U1") (pin "H1") (pinfunction "IOL_14B_H1") (pintype "bidirectional"))
    )
    (net (code "63") (name "/LVDS_9_N") (class "Default")
      (node (ref "R196") (pin "1") (pinfunction "1_1") (pintype "passive"))
      (node (ref "U1") (pin "L4") (pinfunction "IOL_17A_L4") (pintype "bidirectional"))
    )
    (net (code "64") (name "/LVDS_9_P") (class "Default")
      (node (ref "R197") (pin "1") (pinfunction "1_1") (pintype "passive"))
      (node (ref "U1") (pin "L1") (pinfunction "IOL_17B_L1") (pintype "bidirectional"))
    )
    (net (code "65") (name "/LVDS_10_N") (class "Default")
      (node (ref "R198") (pin "1") (pinfunction "1_1") (pintype "passive"))
      (node (ref "U1") (pin "J2") (pinfunction "IOL_15A_J2") (pintype "bidirectional"))
    )
    (net (code "66") (name "/LVDS_10_P") (class "Default")
      (node (ref "R199") (pin "1") (pinfunction "1_1") (pintype "passive"))
      (node (ref "U1") (pin "J1") (pinfunction "IOL_15B_J1") (pintype "bidirectional"))
    )
    (net (code "67") (name "/LVDS_11_N") (class "Default")
      (node (ref "R200") (pin "1") (pinfunction "1_1") (pintype "passive"))
      (node (ref "U1") (pin "H3") (pinfunction "IOL_9A_H3") (pintype "bidirectional"))
    )
    (net (code "68") (name "/LVDS_11_P") (class "Default")
      (node (ref "R203") (pin "1") (pinfunction "1_1") (pintype "passive"))
      (node (ref "U1") (pin "F2") (pinfunction "IOL_9B_F2") (pintype "bidirectional"))
    )
    (net (code "69") (name "/LVDS_12_N") (class "Default")
      (node (ref "R208") (pin "1") (pinfunction "1_1") (pintype "passive"))
      (node (ref "U1") (pin "H5") (pinfunction "IOL_7A_H5") (pintype "bidirectional"))
    )
    (net (code "70") (name "/LVDS_12_P") (class "Default")
      (node (ref "R209") (pin "1") (pinfunction "1_1") (pintype "passive"))
      (node (ref "U1") (pin "E2") (pinfunction "IOL_7B_E2") (pintype "bidirectional"))
    )
    (net (code "71") (name "/LVDS_13_N") (class "Default")
      (node (ref "R210") (pin "1") (pinfunction "1_1") (pintype "passive"))
      (node (ref "U1") (pin "G5") (pinfunction "IOL_5A_G5") (pintype "bidirectional"))
    )
    (net (code "72") (name "/LVDS_13_P") (class "Default")
      (node (ref "R211") (pin "1") (pinfunction "1_1") (pintype "passive"))
      (node (ref "U1") (pin "D1") (pinfunction "IOL_5B_D1") (pintype "bidirectional"))
    )
    (net (code "73") (name "/LVDS_14_N") (class "Default")
      (node (ref "R212") (pin "1") (pinfunction "1_1") (pintype "passive"))
      (node (ref "U1") (pin "C1") (pinfunction "IOL_3A_C1") (pintype "bidirectional"))
    )
    (net (code "74") (name "/LVDS_14_P") (class "Default")
      (node (ref "R213") (pin "1") (pinfunction "1_1") (pintype "passive"))
      (node (ref "U1") (pin "C2") (pinfunction "IOL_3B_C2") (pintype "bidirectional"))
    )
    (net (code "75") (name "/LVDS_15_N") (class "Default")
      (node (ref "R214") (pin "1") (pinfunction "1_1") (pintype "passive"))
      (node (ref "U1") (pin "F5") (pinfunction "IOL_2A_F5") (pintype "bidirectional"))
    )
    (net (code "76") (name "/LVDS_15_P") (class "Default")
      (node (ref "R215") (pin "1") (pinfunction "1_1") (pintype "passive"))
      (node (ref "U1") (pin "B1") (pinfunction "IOL_2B_B1") (pintype "bidirectional"))
    )
    (net (code "77") (name "/OUT_CTRLn0") (class "Default")
      (node (ref "U1") (pin "L3") (pinfunction "IOL_19B_L3") (pintype "bidirectional"))
    )
    (net (code "78") (name "/OUT_CTRLn1") (class "Default")
      (node (ref "U1") (pin "L6") (pinfunction "IOL_19A_L6") (pintype "bidirectional"))
    )
    (net (code "79") (name "/OUT_CTRLn2") (class "Default")
      (node (ref "U1") (pin "M2") (pinfunction "IOL_20B_M2") (pintype "bidirectional"))
    )
    (net (code "80") (name "/OUT_CTRLn3") (class "Default")
      (node (ref "U1") (pin "K5") (pinfunction "IOL_20A_K5") (pintype "bidirectional"))
    )
    (net (code "81") (name "/OUT_CTRLn4") (class "Default")
      (node (ref "U1") (pin "N2") (pinfunction "IOL_21B_N2") (pintype "bidirectional"))
    )
    (net (code "82") (name "/OUT_CTRLn5") (class "Default")
      (node (ref "U1") (pin "L7") (pinfunction "IOL_21A_L7") (pintype "bidirectional"))
    )
    (net (code "83") (name "/OUT_CTRLn6") (class "Default")
      (node (ref "U1") (pin "M3") (pinfunction "IOL_22B_M3") (pintype "bidirectional"))
    )
    (net (code "84") (name "/OUT_CTRLn7") (class "Default")
      (node (ref "U1") (pin "M6") (pinfunction "IOL_22A_M6") (pintype "bidirectional"))
    )
    (net (code "86") (name "/PWR_EN") (class "Default")
      (node (ref "R86") (pin "2") (pinfunction "2_2") (pintype "passive"))
      (node (ref "R89") (pin "2") (pinfunction "2_2") (pintype "passive"))
    )
    (net (code "87") (name "/SERVMOD_3V3") (class "Default")
      (node (ref "IC25") (pin "13") (pinfunction "E_13") (pintype "input"))
      (node (ref "IC25") (pin "5") (pinfunction "E_5") (pintype "input"))
    )
    (net (code "88") (name "/Switch_I2C.SCL") (class "Default")
      (node (ref "IC25") (pin "2") (pinfunction "Z_2") (pintype "bidirectional"))
      (node (ref "R233") (pin "2") (pinfunction "2_2") (pintype "passive"))
    )
    (net (code "89") (name "/Switch_I2C.SDA") (class "Default")
      (node (ref "IC25") (pin "3") (pinfunction "Z_3") (pintype "bidirectional"))
      (node (ref "R3") (pin "2") (pinfunction "2_2") (pintype "passive"))
    )
    (net (code "91") (name "GND") (class "Default")
      (node (ref "C105") (pin "1") (pinfunction "1_1") (pintype "passive"))
      (node (ref "C38") (pin "1") (pinfunction "1_1") (pintype "passive"))
      (node (ref "C47") (pin "1") (pinfunction "1_1") (pintype "passive"))
      (node (ref "D1") (pin "1") (pinfunction "GND_1") (pintype "power_in"))
      (node (ref "IC15") (pin "4") (pinfunction "VSS_4") (pintype "power_in"))
      (node (ref "IC25") (pin "10") (pinfunction "Z_10") (pintype "bidirectional"))
      (node (ref "IC25") (pin "11") (pinfunction "Y_11") (pintype "bidirectional"))
      (node (ref "IC25") (pin "12") (pinfunction "E_12") (pintype "input"))
      (node (ref "IC25") (pin "6") (pinfunction "E_6") (pintype "input"))
      (node (ref "IC25") (pin "7") (pinfunction "GND_7") (pintype "power_in"))
      (node (ref "IC25") (pin "8") (pinfunction "Y_8") (pintype "bidirectional"))
      (node (ref "IC25") (pin "9") (pinfunction "Z_9") (pintype "bidirectional"))
      (node (ref "IC32") (pin "2") (pinfunction "VSS_2") (pintype "power_in"))
      (node (ref "IC7") (pin "4") (pinfunction "GND_4") (pintype "power_in"))
      (node (ref "R90") (pin "1") (pinfunction "1_1") (pintype "passive"))
      (node (ref "R91") (pin "1") (pinfunction "1_1") (pintype "passive"))
      (node (ref "R92") (pin "1") (pinfunction "1_1") (pintype "passive"))
      (node (ref "T16") (pin "2") (pinfunction "S_2") (pintype "passive"))
    )
    (net (code "92") (name "Net-(IC7-A0)") (class "Default")
      (node (ref "IC7") (pin "7") (pinfunction "A0_7") (pintype "input"))
      (node (ref "R92") (pin "2") (pinfunction "2_2") (pintype "passive"))
    )
    (net (code "93") (name "Net-(IC7-A1)") (class "Default")
      (node (ref "IC7") (pin "6") (pinfunction "A1_6") (pintype "input"))
      (node (ref "R91") (pin "2") (pinfunction "2_2") (pintype "passive"))
    )
    (net (code "94") (name "Net-(IC7-A2)") (class "Default")
      (node (ref "IC7") (pin "5") (pinfunction "A2_5") (pintype "input"))
      (node (ref "R90") (pin "2") (pinfunction "2_2") (pintype "passive"))
    )
    (net (code "95") (name "Net-(LD20-A)") (class "Default")
      (node (ref "LD20") (pin "2") (pinfunction "A_2") (pintype "passive"))
      (node (ref "R93") (pin "1") (pinfunction "1_1") (pintype "passive"))
    )
    (net (code "96") (name "Net-(T6-G)") (class "Default")
      (node (ref "R70") (pin "1") (pinfunction "1_1") (pintype "passive"))
      (node (ref "T6") (pin "1") (pinfunction "G_1") (pintype "passive"))
    )
    (net (code "97") (name "Net-(T6-S)") (class "Default")
      (node (ref "R74") (pin "2") (pinfunction "2_2") (pintype "passive"))
      (node (ref "T6") (pin "2") (pinfunction "S_2") (pintype "passive"))
    )
    (net (code "98") (name "Net-(T9-G)") (class "Default")
      (node (ref "R108") (pin "1") (pinfunction "1_1") (pintype "passive"))
      (node (ref "T9") (pin "1") (pinfunction "G_1") (pintype "passive"))
    )
    (net (code "99") (name "Net-(T9-S)") (class "Default")
      (node (ref "R78") (pin "2") (pinfunction "2_2") (pintype "passive"))
      (node (ref "T9") (pin "2") (pinfunction "S_2") (pintype "passive"))
    )
    (net (code "100") (name "Net-(T16-D)") (class "Default")
      (node (ref "R30") (pin "2") (pinfunction "2_2") (pintype "passive"))
      (node (ref "T16") (pin "3") (pinfunction "D_3") (pintype "passive"))
    )
    (net (code "101") (name "P3V3") (class "Default")
      (node (ref "LD19") (pin "2") (pinfunction "A_2") (pintype "passive"))
      (node (ref "R74") (pin "1") (pinfunction "1_1") (pintype "passive"))
      (node (ref "R78") (pin "1") (pinfunction "1_1") (pintype "passive"))
    )
    (net (code "102") (name "P3V3_MP") (class "Default")
      (node (ref "C105") (pin "2") (pinfunction "2_2") (pintype "passive"))
      (node (ref "C38") (pin "2") (pinfunction "2_2") (pintype "passive"))
      (node (ref "C47") (pin "2") (pinfunction "2_2") (pintype "passive"))
      (node (ref "D1") (pin "4") (pinfunction "VCC_4") (pintype "power_in"))
      (node (ref "IC15") (pin "8") (pinfunction "VCC_8") (pintype "power_in"))
      (node (ref "IC25") (pin "14") (pinfunction "VCC_14") (pintype "power_in"))
      (node (ref "IC32") (pin "4") (pinfunction "VCC_4") (pintype "power_in"))
      (node (ref "IC7") (pin "8") (pinfunction "+VS_8") (pintype "power_in"))
      (node (ref "R175") (pin "2") (pinfunction "2_2") (pintype "passive"))
      (node (ref "R177") (pin "2") (pinfunction "2_2") (pintype "passive"))
      (node (ref "R86") (pin "1") (pinfunction "1_1") (pintype "passive"))
      (node (ref "R93") (pin "2") (pinfunction "2_2") (pintype "passive"))
      (node (ref "TP3") (pin "1") (pinfunction "1_1") (pintype "bidirectional"))
    )
    (net (code "103") (name "P12V0A") (class "Default")
      (node (ref "R108") (pin "2") (pinfunction "2_2") (pintype "passive"))
      (node (ref "R70") (pin "2") (pinfunction "2_2") (pintype "passive"))
    )
    (net (code "104") (name "unconnected-(IC15-A0_(NC)-Pad1)") (class "Default")
      (node (ref "IC15") (pin "1") (pinfunction "A0_(NC)_1") (pintype "input+no_connect"))
    )
    (net (code "105") (name "unconnected-(IC15-A1_(NC)-Pad2)") (class "Default")
      (node (ref "IC15") (pin "2") (pinfunction "A1_(NC)_2") (pintype "input+no_connect"))
    )
    (net (code "106") (name "unconnected-(IC15-A2_(NC)-Pad3)") (class "Default")
      (node (ref "IC15") (pin "3") (pinfunction "A2_(NC)_3") (pintype "input+no_connect"))
    )
    (net (code "107") (name "unconnected-(IC15-NC-Pad7)") (class "Default")
      (node (ref "IC15") (pin "7") (pinfunction "NC_7") (pintype "passive"))
    )
    (net (code "108") (name "unconnected-(IC32-NC-Pad5)") (class "Default")
      (node (ref "IC32") (pin "5") (pinfunction "NC_5") (pintype "passive"))
    )
    (net (code "109") (name "unconnected-(U1D-IOL_8A-PadG3)") (class "Default")
      (node (ref "U1") (pin "G3") (pinfunction "IOL_8A_G3") (pintype "bidirectional+no_connect"))
    )
    (net (code "110") (name "unconnected-(U1D-IOL_8B-PadF3)") (class "Default")
      (node (ref "U1") (pin "F3") (pinfunction "IOL_8B_F3") (pintype "bidirectional+no_connect"))
    )
    (net (code "111") (name "unconnected-(U1D-IOL_10A-PadH6)") (class "Default")
      (node (ref "U1") (pin "H6") (pinfunction "IOL_10A_H6") (pintype "bidirectional+no_connect"))
    )
    (net (code "112") (name "unconnected-(U1D-IOL_23A-PadL5)") (class "Default")
      (node (ref "U1") (pin "L5") (pinfunction "IOL_23A_L5") (pintype "bidirectional"))
    )
    (net (code "113") (name "unconnected-(U1D-IOL_23B-PadN3)") (class "Default")
      (node (ref "U1") (pin "N3") (pinfunction "IOL_23B_N3") (pintype "bidirectional"))
    )
    (net (code "114") (name "unconnected-(U1D-IOL_24A-PadP1)") (class "Default")
      (node (ref "U1") (pin "P1") (pinfunction "IOL_24A_P1") (pintype "bidirectional"))
    )
    (net (code "115") (name "unconnected-(U1D-IOL_24B-PadM4)") (class "Default")
      (node (ref "U1") (pin "M4") (pinfunction "IOL_24B_M4") (pintype "bidirectional"))
    )
    (net (code "116") (name "unconnected-(U1D-IOL_25A-PadP2)") (class "Default")
      (node (ref "U1") (pin "P2") (pinfunction "IOL_25A_P2") (pintype "bidirectional"))
    )
    (net (code "117") (name "unconnected-(U1D-IOL_25B-PadM5)") (class "Default")
      (node (ref "U1") (pin "M5") (pinfunction "IOL_25B_M5") (pintype "bidirectional"))
    )
    (net (code "118") (name "unconnected-(U1D-IOL_26A-PadR1)") (class "Default")
      (node (ref "U1") (pin "R1") (pinfunction "IOL_26A_R1") (pintype "bidirectional"))
    )
    (net (code "119") (name "unconnected-(U1D-IOL_26B-PadN4)") (class "Default")
      (node (ref "U1") (pin "N4") (pinfunction "IOL_26B_N4") (pintype "bidirectional"))
    )
  )
)
